# LMX2592.net
KiCad netlist of a schematic drawn in Altium Designer
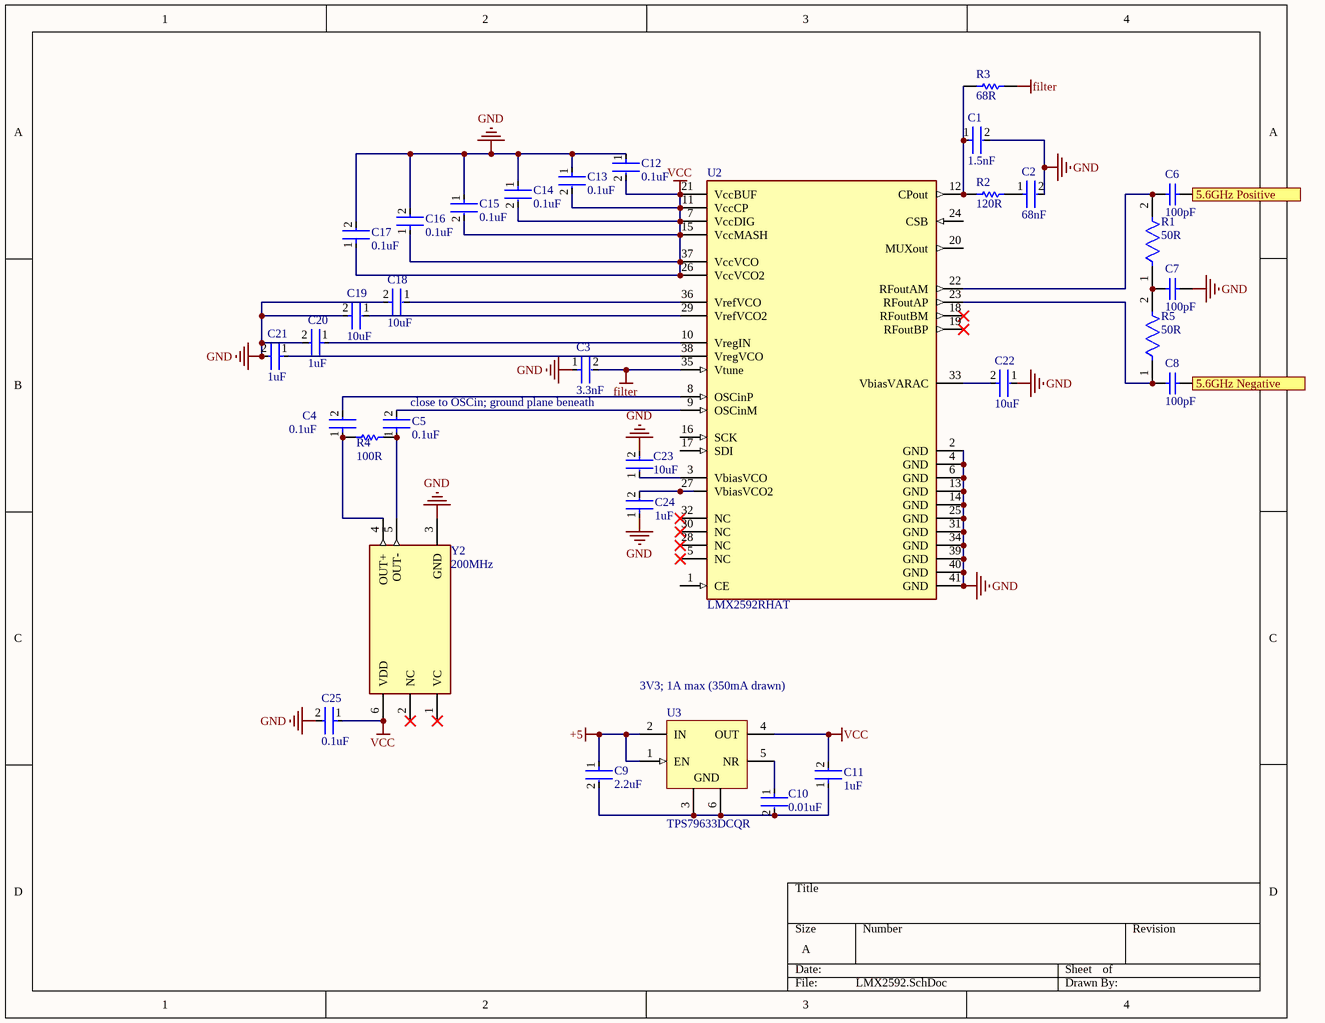
[diagram p0: LMX2592.SchDoc]

(export (version "E")
  (design (tool "Eeschema 10.0.6"))
  (components
    (comp (ref "C1")
      (value "1.5nF")
      (footprint "FP-GRM188-0_1-e0_2_0_5-IPC_B")
      (description "Chip Multilayer Ceramic Capacitors for General Purpose, 0603, 1500pF, C0G, 30ppm/°C, 5%, 50V")
      (fields (field (name "TOLERANCE") "5%") (field (name "VOLTAGE") "50V"))
      (libsource (lib "Altium Content Vault") (part "11868f565c42a9108669ba33697ecf6"))
    )
    (comp (ref "C2")
      (value "68nF")
      (footprint "FP-GRM319-0_15-MFG")
      (description "Chip Multilayer Ceramic Capacitors for General Purpose, 1206, 68000pF, C0G, 30ppm/°C, 5%, 50V")
      (libsource (lib "Altium Content Vault") (part "b4654b650e69147ec39a6b967a45e02"))
    )
    (comp (ref "C3")
      (value "3.3nF")
      (footprint "FP-GCM188-0_1-MFG")
      (description "Ceramic Capacitor for Automotive 3.3nF  ±1% 50VDC C0G 0603 Paper T/R")
      (libsource (lib "Altium Content Vault") (part "02cd4be3c70576c341d710602a673aa"))
    )
    (comp (ref "C4")
      (value "0.1uF")
      (footprint "FP-C0603C-CF-MFG")
      (description "CAP CER 0.1UF 50V X7R 0603")
      (fields (field (name "TOLERANCE") "0.1") (field (name "MANUFACTURER") "KEMET"))
      (libsource (lib "Altium Content Vault") (part "b4654b650e69147ec39a6b967a45e02"))
    )
    (comp (ref "C5")
      (value "0.1uF")
      (footprint "FP-C0603C-CF-MFG")
      (description "CAP CER 0.1UF 50V X7R 0603")
      (fields (field (name "TOLERANCE") "0.1") (field (name "MANUFACTURER") "KEMET"))
      (libsource (lib "Altium Content Vault") (part "b4654b650e69147ec39a6b967a45e02"))
    )
    (comp (ref "C6")
      (value "100pF")
      (footprint "CAPC1608X90X35NL10T15")
      (fields (field (name "PART NUMBER") "GRM1885C1H101JA01D") (field (name "MANUFACTURER") "Murata"))
      (libsource (lib "Altium Content Vault") (part "CAP"))
    )
    (comp (ref "C7")
      (value "100pF")
      (footprint "CAPC1608X90X35NL10T15")
      (fields (field (name "PART NUMBER") "GRM1885C1H101JA01D") (field (name "MANUFACTURER") "Murata"))
      (libsource (lib "Altium Content Vault") (part "CAP"))
    )
    (comp (ref "C8")
      (value "100pF")
      (footprint "CAPC1608X90X35NL10T15")
      (fields (field (name "PART NUMBER") "GRM1885C1H101JA01D") (field (name "MANUFACTURER") "Murata"))
      (libsource (lib "Altium Content Vault") (part "CAP"))
    )
    (comp (ref "C9")
      (value "2.2uF")
      (footprint "FP-GRM188-0_1-e0_2_0_5-MFG")
      (description "Chip Multilayer Ceramic Capacitors for General Purpose, 0603, 2.2uF, X7R, 15%, 10%, 10V")
      (fields (field (name "VOLTAGE") "10V") (field (name "TOLERANCE") "10%"))
      (libsource (lib "Altium Content Vault") (part "11868f565c42a9108669ba33697ecf6"))
    )
    (comp (ref "C10")
      (value "0.01uF")
      (footprint "FP-C0603C-CF-MFG")
      (description "CAP CER 10000PF 50V X7R 0603")
      (fields
        (field (name "MANUFACTURER") "KEMET")
        (field (name "OCTOPART") "https://octopart.com/c0603c103k5ractu-kemet-133094")
      )
      (libsource (lib "Altium Content Vault") (part "b4654b650e69147ec39a6b967a45e02"))
    )
    (comp (ref "C11")
      (value "1uF")
      (footprint "FP-0603-L_1_6_0_15-W_0_8-IPC_C")
      (description "Ceramic Capacitor General Use 1uF ±10% 50V X7R 0603")
      (fields (field (name "TOLERANCE") "10%"))
      (libsource (lib "Altium Content Vault") (part "11868f565c42a9108669ba33697ecf6"))
    )
    (comp (ref "C12")
      (value "0.1uF")
      (footprint "FP-C0603C-CF-MFG")
      (description "CAP CER 0.1UF 50V X7R 0603")
      (fields (field (name "TOLERANCE") "0.1") (field (name "MANUFACTURER") "KEMET"))
      (libsource (lib "Altium Content Vault") (part "b4654b650e69147ec39a6b967a45e02"))
    )
    (comp (ref "C13")
      (value "0.1uF")
      (footprint "FP-C0603C-CF-MFG")
      (description "CAP CER 0.1UF 50V X7R 0603")
      (fields (field (name "TOLERANCE") "0.1") (field (name "MANUFACTURER") "KEMET"))
      (libsource (lib "Altium Content Vault") (part "b4654b650e69147ec39a6b967a45e02"))
    )
    (comp (ref "C14")
      (value "0.1uF")
      (footprint "FP-C0603C-CF-MFG")
      (description "CAP CER 0.1UF 50V X7R 0603")
      (fields (field (name "TOLERANCE") "0.1") (field (name "MANUFACTURER") "KEMET"))
      (libsource (lib "Altium Content Vault") (part "b4654b650e69147ec39a6b967a45e02"))
    )
    (comp (ref "C15")
      (value "0.1uF")
      (footprint "FP-C0603C-CF-MFG")
      (description "CAP CER 0.1UF 50V X7R 0603")
      (fields (field (name "TOLERANCE") "0.1") (field (name "MANUFACTURER") "KEMET"))
      (libsource (lib "Altium Content Vault") (part "b4654b650e69147ec39a6b967a45e02"))
    )
    (comp (ref "C16")
      (value "0.1uF")
      (footprint "FP-C0603C-CF-MFG")
      (description "CAP CER 0.1UF 50V X7R 0603")
      (fields (field (name "TOLERANCE") "0.1") (field (name "MANUFACTURER") "KEMET"))
      (libsource (lib "Altium Content Vault") (part "b4654b650e69147ec39a6b967a45e02"))
    )
    (comp (ref "C17")
      (value "0.1uF")
      (footprint "FP-C0603C-CF-MFG")
      (description "CAP CER 0.1UF 50V X7R 0603")
      (fields (field (name "TOLERANCE") "0.1") (field (name "MANUFACTURER") "KEMET"))
      (libsource (lib "Altium Content Vault") (part "b4654b650e69147ec39a6b967a45e02"))
    )
    (comp (ref "C18")
      (value "10uF")
      (footprint "FP-CL21B106KOQNNNE-MFG")
      (description "CAP CER 10UF 16V X7R 0805")
      (fields
        (field (name "MANUFACTURER PART NUMBER") "CL21B106KOQNNNE")
        (field (name "OCTOPART") "https://octopart.com/cl21b106koqnnne-samsung-19832289")
      )
      (libsource (lib "Altium Content Vault") (part "236180d848d6139a670b325ea6854c9"))
    )
    (comp (ref "C19")
      (value "10uF")
      (footprint "FP-CL21B106KOQNNNE-MFG")
      (description "CAP CER 10UF 16V X7R 0805")
      (fields
        (field (name "MANUFACTURER PART NUMBER") "CL21B106KOQNNNE")
        (field (name "OCTOPART") "https://octopart.com/cl21b106koqnnne-samsung-19832289")
      )
      (libsource (lib "Altium Content Vault") (part "236180d848d6139a670b325ea6854c9"))
    )
    (comp (ref "C20")
      (value "1uF")
      (footprint "FP-0603-L_1_6_0_15-W_0_8-IPC_C")
      (description "Ceramic Capacitor General Use 1uF ±10% 50V X7R 0603")
      (fields (field (name "TOLERANCE") "10%"))
      (libsource (lib "Altium Content Vault") (part "11868f565c42a9108669ba33697ecf6"))
    )
    (comp (ref "C21")
      (value "1uF")
      (footprint "FP-0603-L_1_6_0_15-W_0_8-IPC_C")
      (description "Ceramic Capacitor General Use 1uF ±10% 50V X7R 0603")
      (fields (field (name "TOLERANCE") "10%"))
      (libsource (lib "Altium Content Vault") (part "11868f565c42a9108669ba33697ecf6"))
    )
    (comp (ref "C22")
      (value "10uF")
      (footprint "FP-CL21B106KOQNNNE-MFG")
      (description "CAP CER 10UF 16V X7R 0805")
      (fields
        (field (name "MANUFACTURER PART NUMBER") "CL21B106KOQNNNE")
        (field (name "OCTOPART") "https://octopart.com/cl21b106koqnnne-samsung-19832289")
      )
      (libsource (lib "Altium Content Vault") (part "236180d848d6139a670b325ea6854c9"))
    )
    (comp (ref "C23")
      (value "10uF")
      (footprint "FP-CL21B106KOQNNNE-MFG")
      (description "CAP CER 10UF 16V X7R 0805")
      (fields
        (field (name "MANUFACTURER PART NUMBER") "CL21B106KOQNNNE")
        (field (name "OCTOPART") "https://octopart.com/cl21b106koqnnne-samsung-19832289")
      )
      (libsource (lib "Altium Content Vault") (part "236180d848d6139a670b325ea6854c9"))
    )
    (comp (ref "C24")
      (value "1uF")
      (footprint "FP-0603-L_1_6_0_15-W_0_8-IPC_C")
      (description "Ceramic Capacitor General Use 1uF ±10% 50V X7R 0603")
      (fields (field (name "TOLERANCE") "10%"))
      (libsource (lib "Altium Content Vault") (part "11868f565c42a9108669ba33697ecf6"))
    )
    (comp (ref "C25")
      (value "0.1uF")
      (footprint "FP-C0603C-CF-MFG")
      (description "CAP CER 0.1UF 50V X7R 0603")
      (fields (field (name "TOLERANCE") "0.1") (field (name "MANUFACTURER") "KEMET"))
      (libsource (lib "Altium Content Vault") (part "b4654b650e69147ec39a6b967a45e02"))
    )
    (comp (ref "R1")
      (value "50R")
      (footprint "FP-CRCW0603-e3-MFG")
      (description "RES Thick Film, 50Ω, 1%, 0.1W, 100ppm/°C, 0603")
      (fields (field (name "TOLERANCE") "1%"))
      (libsource (lib "Altium Content Vault") (part "1029c3af85768c4190bb7ad29bc67b5"))
    )
    (comp (ref "R2")
      (value "120R")
      (footprint "RESC1608X55X25NL10T15")
      (description "Chip Resistor, 120 Ohm, +/- 1%, 100 mW, -55 to 155 degC, 0603 (1608 Metric), RoHS, Tape and Reel")
      (libsource (lib "Altium Content Vault") (part "RES-2"))
    )
    (comp (ref "R3")
      (value "68R")
      (footprint "RESC1608X55X30ML15T15")
      (fields (field (name "PART NUMBER") "ERJ-3GEYJ680V") (field (name "MANUFACTURER") "Panasonic"))
      (libsource (lib "Altium Content Vault") (part "RES"))
    )
    (comp (ref "R4")
      (value "100R")
      (footprint "RESC1609X50X30ML8T20")
      (description "Chip Resistor, 100 Ohm, +/- 1%, 100 mW,-55 to 155 degC, 0603 (1608 Metric), RoHS, Tape and Ree")
      (fields (field (name "MANUFACTURER") "Vishay Semiconductor"))
      (libsource (lib "Altium Content Vault") (part "RES-2"))
    )
    (comp (ref "R5")
      (value "50R")
      (footprint "FP-CRCW0603-e3-MFG")
      (description "RES Thick Film, 50Ω, 1%, 0.1W, 100ppm/°C, 0603")
      (fields (field (name "TOLERANCE") "1%"))
      (libsource (lib "Altium Content Vault") (part "1029c3af85768c4190bb7ad29bc67b5"))
    )
    (comp (ref "U2")
      (value "LMX2592RHAT")
      (footprint "FP-RHA0040H-IPC_B")
      (description "IC PLL FREQ SYNTH W/VCO 40VQFN")
      (libsource (lib "Altium Content Vault") (part "9e82714c564c87cee1c1c12d4cd209e"))
    )
    (comp (ref "U3")
      (value "TPS79633DCQR")
      (footprint "DCQ0006A_L")
      (fields (field (name "MANUFACTURER") "Texas Instruments"))
      (libsource (lib "Altium Content Vault") (part "TI-TPS7XXXXXXXX"))
    )
    (comp (ref "Y2")
      (value "200MHz")
      (footprint "FP-SiT5021AI-MFG")
      (description "MEMS OSC VCTCXO 200.0000MHZ LVDS")
      (libsource (lib "Altium Content Vault") (part "a0ff00efb61d16d854f6ec510733f8b"))
    )
  )
  (nets
    (net (code "1") (name "+5") (class "Default")
      (node (ref "C9") (pin "1") (pinfunction "1_1") (pintype "passive"))
      (node (ref "U3") (pin "1") (pinfunction "EN_1") (pintype "input"))
      (node (ref "U3") (pin "2") (pinfunction "IN_2") (pintype "power_in"))
    )
    (net (code "2") (name "/5.6GHz Negative") (class "Default")
      (node (ref "C8") (pin "2") (pinfunction "2_2") (pintype "passive"))
    )
    (net (code "3") (name "/5.6GHz Positive") (class "Default")
      (node (ref "C6") (pin "2") (pinfunction "2_2") (pintype "passive"))
    )
    (net (code "4") (name "GND") (class "Default")
      (node (ref "C1") (pin "2") (pinfunction "2_2") (pintype "passive"))
      (node (ref "C12") (pin "1") (pinfunction "1_1") (pintype "passive"))
      (node (ref "C13") (pin "1") (pinfunction "1_1") (pintype "passive"))
      (node (ref "C14") (pin "1") (pinfunction "1_1") (pintype "passive"))
      (node (ref "C15") (pin "1") (pinfunction "1_1") (pintype "passive"))
      (node (ref "C16") (pin "2") (pinfunction "2_2") (pintype "passive"))
      (node (ref "C17") (pin "2") (pinfunction "2_2") (pintype "passive"))
      (node (ref "C18") (pin "2") (pinfunction "2_2") (pintype "passive"))
      (node (ref "C19") (pin "2") (pinfunction "2_2") (pintype "passive"))
      (node (ref "C2") (pin "2") (pinfunction "2_2") (pintype "passive"))
      (node (ref "C20") (pin "2") (pinfunction "2_2") (pintype "passive"))
      (node (ref "C21") (pin "2") (pinfunction "2_2") (pintype "passive"))
      (node (ref "C22") (pin "1") (pinfunction "1_1") (pintype "passive"))
      (node (ref "C23") (pin "2") (pinfunction "2_2") (pintype "passive"))
      (node (ref "C24") (pin "1") (pinfunction "1_1") (pintype "passive"))
      (node (ref "C25") (pin "2") (pinfunction "2_2") (pintype "passive"))
      (node (ref "C3") (pin "1") (pinfunction "1_1") (pintype "passive"))
      (node (ref "C7") (pin "2") (pinfunction "2_2") (pintype "passive"))
      (node (ref "U2") (pin "13") (pinfunction "GND_13") (pintype "power_in"))
      (node (ref "U2") (pin "14") (pinfunction "GND_14") (pintype "power_in"))
      (node (ref "U2") (pin "2") (pinfunction "GND_2") (pintype "power_in"))
      (node (ref "U2") (pin "25") (pinfunction "GND_25") (pintype "power_in"))
      (node (ref "U2") (pin "31") (pinfunction "GND_31") (pintype "power_in"))
      (node (ref "U2") (pin "34") (pinfunction "GND_34") (pintype "power_in"))
      (node (ref "U2") (pin "39") (pinfunction "GND_39") (pintype "power_in"))
      (node (ref "U2") (pin "4") (pinfunction "GND_4") (pintype "power_in"))
      (node (ref "U2") (pin "40") (pinfunction "GND_40") (pintype "power_in"))
      (node (ref "U2") (pin "41") (pinfunction "GND_41") (pintype "power_in"))
      (node (ref "U2") (pin "6") (pinfunction "GND_6") (pintype "power_in"))
      (node (ref "Y2") (pin "3") (pinfunction "GND_3") (pintype "power_in"))
    )
    (net (code "5") (name "Net-(C2-Pad1)") (class "Default")
      (node (ref "C2") (pin "1") (pinfunction "1_1") (pintype "passive"))
      (node (ref "R2") (pin "2") (pinfunction "2_2") (pintype "passive"))
    )
    (net (code "6") (name "Net-(C7-Pad1)") (class "Default")
      (node (ref "C7") (pin "1") (pinfunction "1_1") (pintype "passive"))
      (node (ref "R1") (pin "1") (pinfunction "1_1") (pintype "passive"))
      (node (ref "R5") (pin "2") (pinfunction "2_2") (pintype "passive"))
    )
    (net (code "7") (name "Net-(C10-Pad2)") (class "Default")
      (node (ref "C10") (pin "2") (pinfunction "2_2") (pintype "passive"))
      (node (ref "C11") (pin "1") (pinfunction "1_1") (pintype "passive"))
      (node (ref "C9") (pin "2") (pinfunction "2_2") (pintype "passive"))
      (node (ref "U3") (pin "3") (pinfunction "GND_3") (pintype "power_in"))
      (node (ref "U3") (pin "6") (pinfunction "GND_6") (pintype "power_in"))
    )
    (net (code "8") (name "Net-(U2-CPout)") (class "Default")
      (node (ref "C1") (pin "1") (pinfunction "1_1") (pintype "passive"))
      (node (ref "R2") (pin "1") (pinfunction "1_1") (pintype "passive"))
      (node (ref "R3") (pin "1") (pinfunction "1_1") (pintype "passive"))
      (node (ref "U2") (pin "12") (pinfunction "CPout_12") (pintype "output"))
    )
    (net (code "9") (name "Net-(U2-OSCinM)") (class "Default")
      (node (ref "C5") (pin "2") (pinfunction "2_2") (pintype "passive"))
      (node (ref "U2") (pin "9") (pinfunction "OSCinM_9") (pintype "input"))
    )
    (net (code "10") (name "Net-(U2-OSCinP)") (class "Default")
      (node (ref "C4") (pin "2") (pinfunction "2_2") (pintype "passive"))
      (node (ref "U2") (pin "8") (pinfunction "OSCinP_8") (pintype "input"))
    )
    (net (code "11") (name "Net-(U2-RFoutAM)") (class "Default")
      (node (ref "C6") (pin "1") (pinfunction "1_1") (pintype "passive"))
      (node (ref "R1") (pin "2") (pinfunction "2_2") (pintype "passive"))
      (node (ref "U2") (pin "22") (pinfunction "RFoutAM_22") (pintype "output"))
    )
    (net (code "12") (name "Net-(U2-RFoutAP)") (class "Default")
      (node (ref "C8") (pin "1") (pinfunction "1_1") (pintype "passive"))
      (node (ref "R5") (pin "1") (pinfunction "1_1") (pintype "passive"))
      (node (ref "U2") (pin "23") (pinfunction "RFoutAP_23") (pintype "output"))
    )
    (net (code "13") (name "Net-(U2-VbiasVARAC)") (class "Default")
      (node (ref "C22") (pin "2") (pinfunction "2_2") (pintype "passive"))
      (node (ref "U2") (pin "33") (pinfunction "VbiasVARAC_33") (pintype "passive"))
    )
    (net (code "14") (name "Net-(U2-VbiasVCO)") (class "Default")
      (node (ref "C23") (pin "1") (pinfunction "1_1") (pintype "passive"))
      (node (ref "U2") (pin "3") (pinfunction "VbiasVCO_3") (pintype "passive"))
    )
    (net (code "15") (name "Net-(U2-VbiasVCO2)") (class "Default")
      (node (ref "C24") (pin "2") (pinfunction "2_2") (pintype "passive"))
      (node (ref "U2") (pin "27") (pinfunction "VbiasVCO2_27") (pintype "passive"))
    )
    (net (code "16") (name "Net-(U2-VrefVCO)") (class "Default")
      (node (ref "C18") (pin "1") (pinfunction "1_1") (pintype "passive"))
      (node (ref "U2") (pin "36") (pinfunction "VrefVCO_36") (pintype "passive"))
    )
    (net (code "17") (name "Net-(U2-VrefVCO2)") (class "Default")
      (node (ref "C19") (pin "1") (pinfunction "1_1") (pintype "passive"))
      (node (ref "U2") (pin "29") (pinfunction "VrefVCO2_29") (pintype "passive"))
    )
    (net (code "18") (name "Net-(U2-VregIN)") (class "Default")
      (node (ref "C20") (pin "1") (pinfunction "1_1") (pintype "passive"))
      (node (ref "U2") (pin "10") (pinfunction "VregIN_10") (pintype "passive"))
    )
    (net (code "19") (name "Net-(U2-VregVCO)") (class "Default")
      (node (ref "C21") (pin "1") (pinfunction "1_1") (pintype "passive"))
      (node (ref "U2") (pin "38") (pinfunction "VregVCO_38") (pintype "passive"))
    )
    (net (code "20") (name "Net-(U3-NR)") (class "Default")
      (node (ref "C10") (pin "1") (pinfunction "1_1") (pintype "passive"))
      (node (ref "U3") (pin "5") (pinfunction "NR_5") (pintype "passive"))
    )
    (net (code "21") (name "Net-(Y2-OUT+)") (class "Default")
      (node (ref "C4") (pin "1") (pinfunction "1_1") (pintype "passive"))
      (node (ref "R4") (pin "1") (pinfunction "1_1") (pintype "passive"))
      (node (ref "Y2") (pin "4") (pinfunction "OUT+_4") (pintype "output"))
    )
    (net (code "22") (name "Net-(Y2-OUT-)") (class "Default")
      (node (ref "C5") (pin "1") (pinfunction "1_1") (pintype "passive"))
      (node (ref "R4") (pin "2") (pinfunction "2_2") (pintype "passive"))
      (node (ref "Y2") (pin "5") (pinfunction "OUT-_5") (pintype "output"))
    )
    (net (code "23") (name "VCC") (class "Default")
      (node (ref "C11") (pin "2") (pinfunction "2_2") (pintype "passive"))
      (node (ref "C12") (pin "2") (pinfunction "2_2") (pintype "passive"))
      (node (ref "C13") (pin "2") (pinfunction "2_2") (pintype "passive"))
      (node (ref "C14") (pin "2") (pinfunction "2_2") (pintype "passive"))
      (node (ref "C15") (pin "2") (pinfunction "2_2") (pintype "passive"))
      (node (ref "C16") (pin "1") (pinfunction "1_1") (pintype "passive"))
      (node (ref "C17") (pin "1") (pinfunction "1_1") (pintype "passive"))
      (node (ref "C25") (pin "1") (pinfunction "1_1") (pintype "passive"))
      (node (ref "U2") (pin "11") (pinfunction "VccCP_11") (pintype "power_in"))
      (node (ref "U2") (pin "15") (pinfunction "VccMASH_15") (pintype "power_in"))
      (node (ref "U2") (pin "21") (pinfunction "VccBUF_21") (pintype "power_in"))
      (node (ref "U2") (pin "26") (pinfunction "VccVCO2_26") (pintype "power_in"))
      (node (ref "U2") (pin "37") (pinfunction "VccVCO_37") (pintype "passive"))
      (node (ref "U2") (pin "7") (pinfunction "VccDIG_7") (pintype "power_in"))
      (node (ref "U3") (pin "4") (pinfunction "OUT_4") (pintype "power_in"))
      (node (ref "Y2") (pin "6") (pinfunction "VDD_6") (pintype "power_in"))
    )
    (net (code "24") (name "filter") (class "Default")
      (node (ref "C3") (pin "2") (pinfunction "2_2") (pintype "passive"))
      (node (ref "R3") (pin "2") (pinfunction "2_2") (pintype "passive"))
      (node (ref "U2") (pin "35") (pinfunction "Vtune_35") (pintype "input"))
    )
    (net (code "25") (name "unconnected-(U2-CE-Pad1)") (class "Default")
      (node (ref "U2") (pin "1") (pinfunction "CE_1") (pintype "input"))
    )
    (net (code "26") (name "unconnected-(U2-CSB-Pad24)") (class "Default")
      (node (ref "U2") (pin "24") (pinfunction "CSB_24") (pintype "input"))
    )
    (net (code "27") (name "unconnected-(U2-MUXout-Pad20)") (class "Default")
      (node (ref "U2") (pin "20") (pinfunction "MUXout_20") (pintype "output"))
    )
    (net (code "28") (name "unconnected-(U2-NC-Pad5)") (class "Default")
      (node (ref "U2") (pin "5") (pinfunction "NC_5") (pintype "passive+no_connect"))
    )
    (net (code "29") (name "unconnected-(U2-NC-Pad28)") (class "Default")
      (node (ref "U2") (pin "28") (pinfunction "NC_28") (pintype "passive+no_connect"))
    )
    (net (code "30") (name "unconnected-(U2-NC-Pad30)") (class "Default")
      (node (ref "U2") (pin "30") (pinfunction "NC_30") (pintype "passive+no_connect"))
    )
    (net (code "31") (name "unconnected-(U2-NC-Pad32)") (class "Default")
      (node (ref "U2") (pin "32") (pinfunction "NC_32") (pintype "passive+no_connect"))
    )
    (net (code "32") (name "unconnected-(U2-RFoutBM-Pad18)") (class "Default")
      (node (ref "U2") (pin "18") (pinfunction "RFoutBM_18") (pintype "output+no_connect"))
    )
    (net (code "33") (name "unconnected-(U2-RFoutBP-Pad19)") (class "Default")
      (node (ref "U2") (pin "19") (pinfunction "RFoutBP_19") (pintype "output+no_connect"))
    )
    (net (code "34") (name "unconnected-(U2-SCK-Pad16)") (class "Default")
      (node (ref "U2") (pin "16") (pinfunction "SCK_16") (pintype "input"))
    )
    (net (code "35") (name "unconnected-(U2-SDI-Pad17)") (class "Default")
      (node (ref "U2") (pin "17") (pinfunction "SDI_17") (pintype "input"))
    )
    (net (code "36") (name "unconnected-(Y2-NC-Pad2)") (class "Default")
      (node (ref "Y2") (pin "2") (pinfunction "NC_2") (pintype "passive+no_connect"))
    )
    (net (code "37") (name "unconnected-(Y2-VC-Pad1)") (class "Default")
      (node (ref "Y2") (pin "1") (pinfunction "VC_1") (pintype "passive+no_connect"))
    )
  )
)
